# cell_fuses.net
KiCad netlist of a schematic drawn in Altium Designer
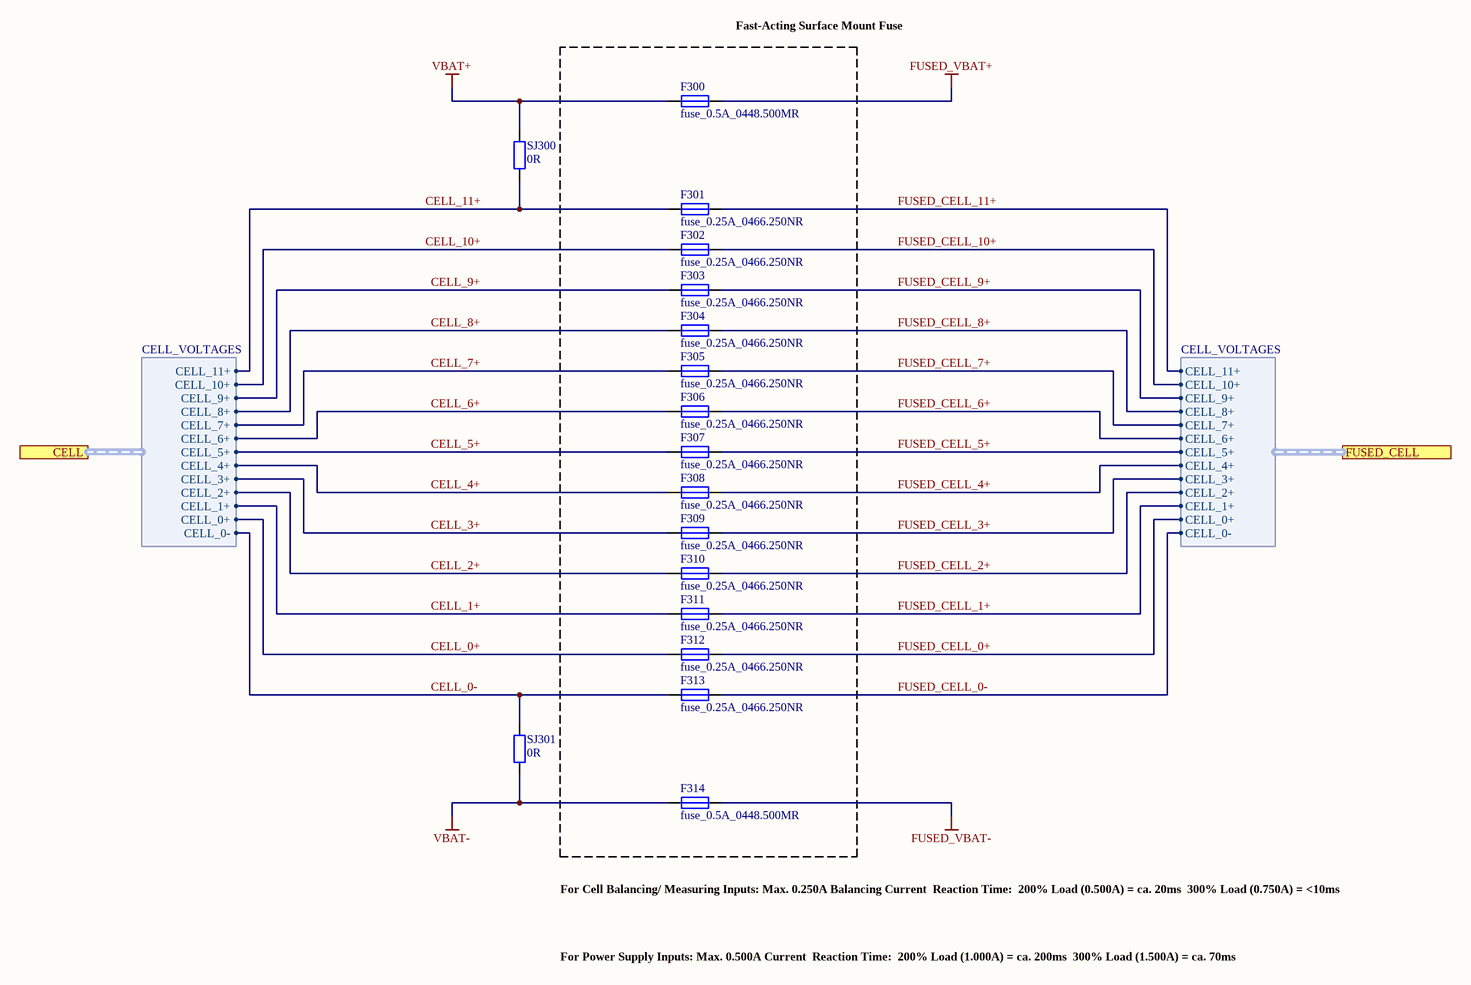
[diagram p0: cell_fuses.SchDoc]

(export (version "E")
  (design (tool "Eeschema 10.0.6"))
  (components
    (comp (ref "F300")
      (value "fuse_0.5A_0448.500MR")
      (footprint "LITTLEFUSE_448")
      (description "Fuse, Surface Mount, NANO2 Series, 500 mA, 125 VAC, 32 VDC, Very Fast Acting, SMD")
      (fields (field (name "MANUFACTURER") "Littlefuse"))
      (libsource (lib "OE750") (part "R_Fuse"))
    )
    (comp (ref "F301")
      (value "fuse_0.25A_0466.250NR")
      (footprint "LITTLEFUSE_466")
      (description "Fuse, Surface Mount, 466 Series, 250 mA, 125 VAC, 125 VDC, Very Fast Acting, 1206")
      (fields (field (name "MANUFACTURER") "Littlefuse"))
      (libsource (lib "OE750") (part "R_Fuse"))
    )
    (comp (ref "F302")
      (value "fuse_0.25A_0466.250NR")
      (footprint "LITTLEFUSE_466")
      (description "Fuse, Surface Mount, 466 Series, 250 mA, 125 VAC, 125 VDC, Very Fast Acting, 1206")
      (fields (field (name "MANUFACTURER") "Littlefuse"))
      (libsource (lib "OE750") (part "R_Fuse"))
    )
    (comp (ref "F303")
      (value "fuse_0.25A_0466.250NR")
      (footprint "LITTLEFUSE_466")
      (description "Fuse, Surface Mount, 466 Series, 250 mA, 125 VAC, 125 VDC, Very Fast Acting, 1206")
      (fields (field (name "MANUFACTURER") "Littlefuse"))
      (libsource (lib "OE750") (part "R_Fuse"))
    )
    (comp (ref "F304")
      (value "fuse_0.25A_0466.250NR")
      (footprint "LITTLEFUSE_466")
      (description "Fuse, Surface Mount, 466 Series, 250 mA, 125 VAC, 125 VDC, Very Fast Acting, 1206")
      (fields (field (name "MANUFACTURER") "Littlefuse"))
      (libsource (lib "OE750") (part "R_Fuse"))
    )
    (comp (ref "F305")
      (value "fuse_0.25A_0466.250NR")
      (footprint "LITTLEFUSE_466")
      (description "Fuse, Surface Mount, 466 Series, 250 mA, 125 VAC, 125 VDC, Very Fast Acting, 1206")
      (fields (field (name "MANUFACTURER") "Littlefuse"))
      (libsource (lib "OE750") (part "R_Fuse"))
    )
    (comp (ref "F306")
      (value "fuse_0.25A_0466.250NR")
      (footprint "LITTLEFUSE_466")
      (description "Fuse, Surface Mount, 466 Series, 250 mA, 125 VAC, 125 VDC, Very Fast Acting, 1206")
      (fields (field (name "MANUFACTURER") "Littlefuse"))
      (libsource (lib "OE750") (part "R_Fuse"))
    )
    (comp (ref "F307")
      (value "fuse_0.25A_0466.250NR")
      (footprint "LITTLEFUSE_466")
      (description "Fuse, Surface Mount, 466 Series, 250 mA, 125 VAC, 125 VDC, Very Fast Acting, 1206")
      (fields (field (name "MANUFACTURER") "Littlefuse"))
      (libsource (lib "OE750") (part "R_Fuse"))
    )
    (comp (ref "F308")
      (value "fuse_0.25A_0466.250NR")
      (footprint "LITTLEFUSE_466")
      (description "Fuse, Surface Mount, 466 Series, 250 mA, 125 VAC, 125 VDC, Very Fast Acting, 1206")
      (fields (field (name "MANUFACTURER") "Littlefuse"))
      (libsource (lib "OE750") (part "R_Fuse"))
    )
    (comp (ref "F309")
      (value "fuse_0.25A_0466.250NR")
      (footprint "LITTLEFUSE_466")
      (description "Fuse, Surface Mount, 466 Series, 250 mA, 125 VAC, 125 VDC, Very Fast Acting, 1206")
      (fields (field (name "MANUFACTURER") "Littlefuse"))
      (libsource (lib "OE750") (part "R_Fuse"))
    )
    (comp (ref "F310")
      (value "fuse_0.25A_0466.250NR")
      (footprint "LITTLEFUSE_466")
      (description "Fuse, Surface Mount, 466 Series, 250 mA, 125 VAC, 125 VDC, Very Fast Acting, 1206")
      (fields (field (name "MANUFACTURER") "Littlefuse"))
      (libsource (lib "OE750") (part "R_Fuse"))
    )
    (comp (ref "F311")
      (value "fuse_0.25A_0466.250NR")
      (footprint "LITTLEFUSE_466")
      (description "Fuse, Surface Mount, 466 Series, 250 mA, 125 VAC, 125 VDC, Very Fast Acting, 1206")
      (fields (field (name "MANUFACTURER") "Littlefuse"))
      (libsource (lib "OE750") (part "R_Fuse"))
    )
    (comp (ref "F312")
      (value "fuse_0.25A_0466.250NR")
      (footprint "LITTLEFUSE_466")
      (description "Fuse, Surface Mount, 466 Series, 250 mA, 125 VAC, 125 VDC, Very Fast Acting, 1206")
      (fields (field (name "MANUFACTURER") "Littlefuse"))
      (libsource (lib "OE750") (part "R_Fuse"))
    )
    (comp (ref "F313")
      (value "fuse_0.25A_0466.250NR")
      (footprint "LITTLEFUSE_466")
      (description "Fuse, Surface Mount, 466 Series, 250 mA, 125 VAC, 125 VDC, Very Fast Acting, 1206")
      (fields (field (name "MANUFACTURER") "Littlefuse"))
      (libsource (lib "OE750") (part "R_Fuse"))
    )
    (comp (ref "F314")
      (value "fuse_0.5A_0448.500MR")
      (footprint "LITTLEFUSE_448")
      (description "Fuse, Surface Mount, NANO2 Series, 500 mA, 125 VAC, 32 VDC, Very Fast Acting, SMD")
      (fields (field (name "MANUFACTURER") "Littlefuse"))
      (libsource (lib "OE750") (part "R_Fuse"))
    )
    (comp (ref "SJ300")
      (value "0R")
      (footprint "RESC1608X05N")
      (description "SMD Resistor 0R 0603")
      (fields (field (name "PART NUMBER") "gen_R_0R_0603") (field (name "POWER") "0.1W"))
      (libsource (lib "OE750") (part "R"))
    )
    (comp (ref "SJ301")
      (value "0R")
      (footprint "RESC1608X05N")
      (description "SMD Resistor 0R 0603")
      (fields (field (name "PART NUMBER") "gen_R_0R_0603") (field (name "POWER") "0.1W"))
      (libsource (lib "OE750") (part "R"))
    )
  )
  (nets
    (net (code "2") (name "/CELL_0+") (class "Default")
      (node (ref "F312") (pin "1") (pinfunction "1_1") (pintype "passive"))
    )
    (net (code "3") (name "/CELL_0-") (class "Default")
      (node (ref "F313") (pin "1") (pinfunction "1_1") (pintype "passive"))
      (node (ref "SJ301") (pin "1") (pinfunction "1_1") (pintype "passive"))
    )
    (net (code "4") (name "/CELL_1+") (class "Default")
      (node (ref "F311") (pin "1") (pinfunction "1_1") (pintype "passive"))
    )
    (net (code "5") (name "/CELL_2+") (class "Default")
      (node (ref "F310") (pin "1") (pinfunction "1_1") (pintype "passive"))
    )
    (net (code "6") (name "/CELL_3+") (class "Default")
      (node (ref "F309") (pin "1") (pinfunction "1_1") (pintype "passive"))
    )
    (net (code "7") (name "/CELL_4+") (class "Default")
      (node (ref "F308") (pin "1") (pinfunction "1_1") (pintype "passive"))
    )
    (net (code "8") (name "/CELL_5+") (class "Default")
      (node (ref "F307") (pin "1") (pinfunction "1_1") (pintype "passive"))
    )
    (net (code "9") (name "/CELL_6+") (class "Default")
      (node (ref "F306") (pin "1") (pinfunction "1_1") (pintype "passive"))
    )
    (net (code "10") (name "/CELL_7+") (class "Default")
      (node (ref "F305") (pin "1") (pinfunction "1_1") (pintype "passive"))
    )
    (net (code "11") (name "/CELL_8+") (class "Default")
      (node (ref "F304") (pin "1") (pinfunction "1_1") (pintype "passive"))
    )
    (net (code "12") (name "/CELL_9+") (class "Default")
      (node (ref "F303") (pin "1") (pinfunction "1_1") (pintype "passive"))
    )
    (net (code "13") (name "/CELL_10+") (class "Default")
      (node (ref "F302") (pin "1") (pinfunction "1_1") (pintype "passive"))
    )
    (net (code "14") (name "/CELL_11+") (class "Default")
      (node (ref "F301") (pin "1") (pinfunction "1_1") (pintype "passive"))
      (node (ref "SJ300") (pin "2") (pinfunction "2_2") (pintype "passive"))
    )
    (net (code "15") (name "/FUSED_CELL_0+") (class "Default")
      (node (ref "F312") (pin "2") (pinfunction "2_2") (pintype "passive"))
    )
    (net (code "16") (name "/FUSED_CELL_0-") (class "Default")
      (node (ref "F313") (pin "2") (pinfunction "2_2") (pintype "passive"))
    )
    (net (code "17") (name "/FUSED_CELL_1+") (class "Default")
      (node (ref "F311") (pin "2") (pinfunction "2_2") (pintype "passive"))
    )
    (net (code "18") (name "/FUSED_CELL_2+") (class "Default")
      (node (ref "F310") (pin "2") (pinfunction "2_2") (pintype "passive"))
    )
    (net (code "19") (name "/FUSED_CELL_3+") (class "Default")
      (node (ref "F309") (pin "2") (pinfunction "2_2") (pintype "passive"))
    )
    (net (code "20") (name "/FUSED_CELL_4+") (class "Default")
      (node (ref "F308") (pin "2") (pinfunction "2_2") (pintype "passive"))
    )
    (net (code "21") (name "/FUSED_CELL_5+") (class "Default")
      (node (ref "F307") (pin "2") (pinfunction "2_2") (pintype "passive"))
    )
    (net (code "22") (name "/FUSED_CELL_6+") (class "Default")
      (node (ref "F306") (pin "2") (pinfunction "2_2") (pintype "passive"))
    )
    (net (code "23") (name "/FUSED_CELL_7+") (class "Default")
      (node (ref "F305") (pin "2") (pinfunction "2_2") (pintype "passive"))
    )
    (net (code "24") (name "/FUSED_CELL_8+") (class "Default")
      (node (ref "F304") (pin "2") (pinfunction "2_2") (pintype "passive"))
    )
    (net (code "25") (name "/FUSED_CELL_9+") (class "Default")
      (node (ref "F303") (pin "2") (pinfunction "2_2") (pintype "passive"))
    )
    (net (code "26") (name "/FUSED_CELL_10+") (class "Default")
      (node (ref "F302") (pin "2") (pinfunction "2_2") (pintype "passive"))
    )
    (net (code "27") (name "/FUSED_CELL_11+") (class "Default")
      (node (ref "F301") (pin "2") (pinfunction "2_2") (pintype "passive"))
    )
    (net (code "29") (name "FUSED_VBAT+") (class "Default")
      (node (ref "F300") (pin "2") (pinfunction "2_2") (pintype "passive"))
    )
    (net (code "30") (name "FUSED_VBAT-") (class "Default")
      (node (ref "F314") (pin "2") (pinfunction "2_2") (pintype "passive"))
    )
    (net (code "31") (name "VBAT+") (class "Default")
      (node (ref "F300") (pin "1") (pinfunction "1_1") (pintype "passive"))
      (node (ref "SJ300") (pin "1") (pinfunction "1_1") (pintype "passive"))
    )
    (net (code "32") (name "VBAT-") (class "Default")
      (node (ref "F314") (pin "1") (pinfunction "1_1") (pintype "passive"))
      (node (ref "SJ301") (pin "2") (pinfunction "2_2") (pintype "passive"))
    )
  )
)
